# 1_1_4_Interface_board_USB_XBee_RS232.net
KiCad netlist of a schematic drawn in Altium Designer
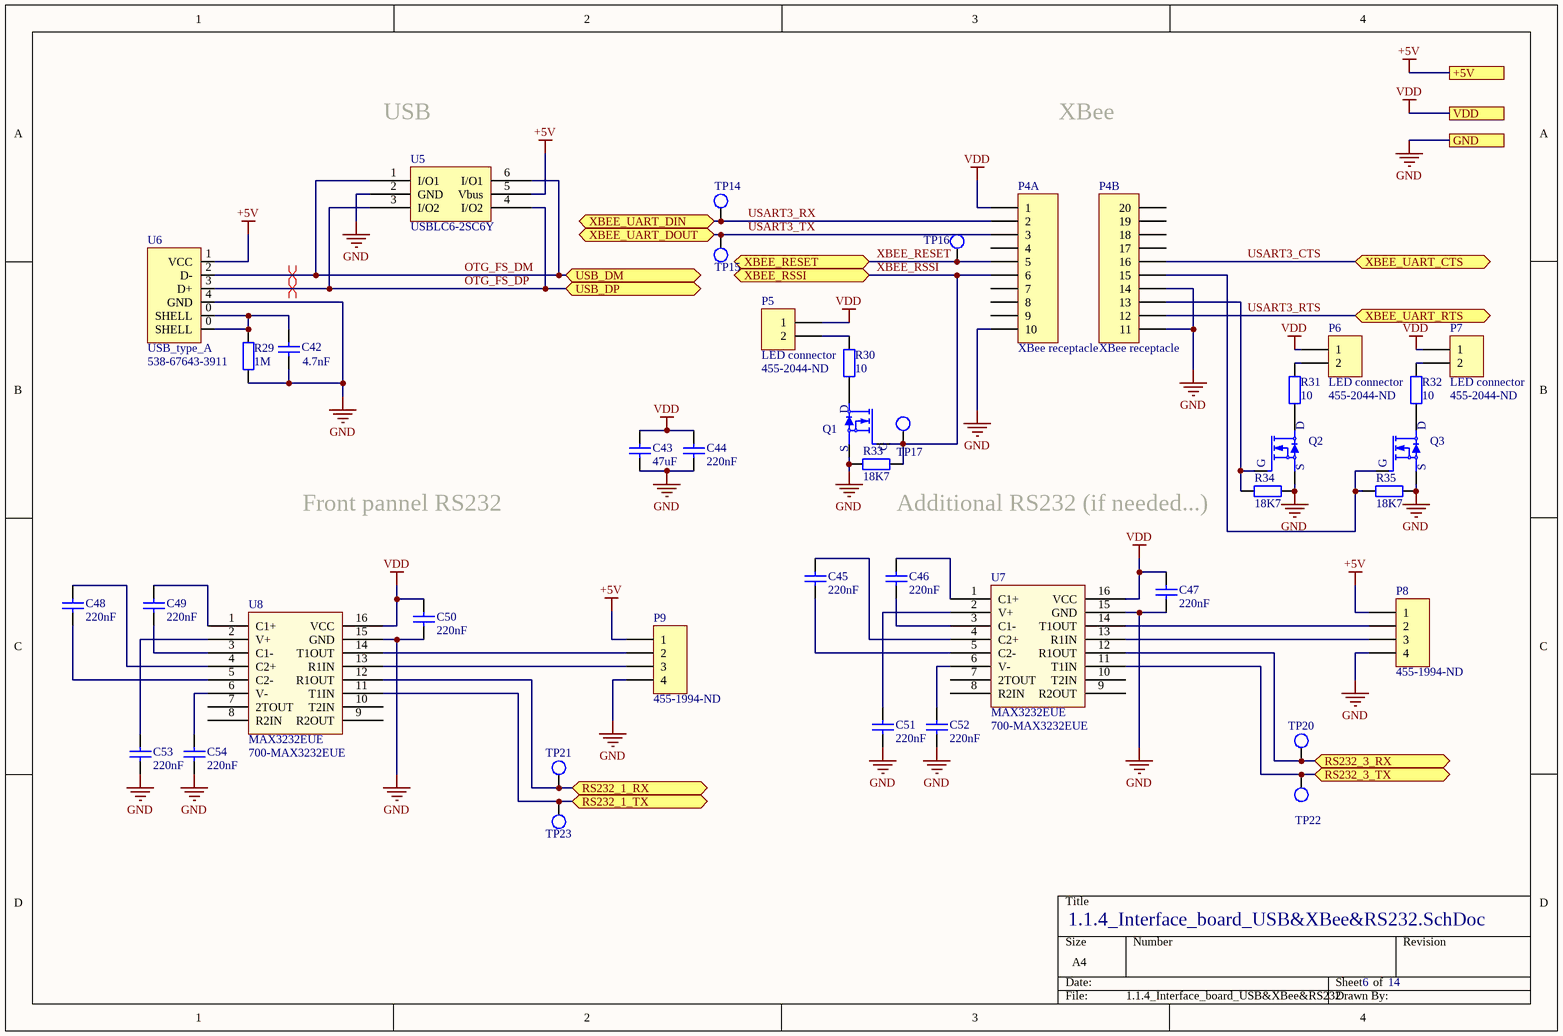
[diagram p0: 1.1.4_Interface_board_USB&XBee&RS232.SchDoc]

(export (version "E")
  (design (tool "Eeschema 10.0.6"))
  (components
    (comp (ref "C42")
      (value "4.7nF")
      (footprint "CAP0603R")
      (description "Capacitor")
      (libsource (lib "Rocket_library") (part "C_4.7nF"))
    )
    (comp (ref "C43")
      (value "47uF")
      (footprint "CAP1206W")
      (description "Capacitor")
      (libsource (lib "Rocket_library") (part "C_47uF_25v_1206"))
    )
    (comp (ref "C44")
      (value "220nF")
      (footprint "CAP0603R")
      (description "Capacitor")
      (libsource (lib "Rocket_library") (part "C_220nF"))
    )
    (comp (ref "C45")
      (value "220nF")
      (footprint "CAP0603R")
      (description "Capacitor")
      (libsource (lib "Rocket_library") (part "C_220nF"))
    )
    (comp (ref "C46")
      (value "220nF")
      (footprint "CAP0603R")
      (description "Capacitor")
      (libsource (lib "Rocket_library") (part "C_220nF"))
    )
    (comp (ref "C47")
      (value "220nF")
      (footprint "CAP0603R")
      (description "Capacitor")
      (libsource (lib "Rocket_library") (part "C_220nF"))
    )
    (comp (ref "C48")
      (value "220nF")
      (footprint "CAP0603R")
      (description "Capacitor")
      (libsource (lib "Rocket_library") (part "C_220nF"))
    )
    (comp (ref "C49")
      (value "220nF")
      (footprint "CAP0603R")
      (description "Capacitor")
      (libsource (lib "Rocket_library") (part "C_220nF"))
    )
    (comp (ref "C50")
      (value "220nF")
      (footprint "CAP0603R")
      (description "Capacitor")
      (libsource (lib "Rocket_library") (part "C_220nF"))
    )
    (comp (ref "C51")
      (value "220nF")
      (footprint "CAP0603R")
      (description "Capacitor")
      (libsource (lib "Rocket_library") (part "C_220nF"))
    )
    (comp (ref "C52")
      (value "220nF")
      (footprint "CAP0603R")
      (description "Capacitor")
      (libsource (lib "Rocket_library") (part "C_220nF"))
    )
    (comp (ref "C53")
      (value "220nF")
      (footprint "CAP0603R")
      (description "Capacitor")
      (libsource (lib "Rocket_library") (part "C_220nF"))
    )
    (comp (ref "C54")
      (value "220nF")
      (footprint "CAP0603R")
      (description "Capacitor")
      (libsource (lib "Rocket_library") (part "C_220nF"))
    )
    (comp (ref "P4")
      (value "XBee receptacle")
      (footprint "XBee receptacle")
      (libsource (lib "Rocket_library") (part "XBee receptacle"))
    )
    (comp (ref "P5")
      (value "LED connector")
      (footprint "CON_JST_XA_ S02B-XASS-1")
      (description "Header 2p JST XA 3A right angle")
      (fields (field (name "SUPPLIER PART NUMBER 1") "455-2044-ND"))
      (libsource (lib "") (part "Header 2p JST XA 3A right angle_1"))
    )
    (comp (ref "P6")
      (value "LED connector")
      (footprint "CON_JST_XA_ S02B-XASS-1")
      (description "Header 2p JST XA 3A right angle")
      (fields (field (name "SUPPLIER PART NUMBER 1") "455-2044-ND"))
      (libsource (lib "Rocket_library") (part "Header 2p JST XA 3A right angle"))
    )
    (comp (ref "P7")
      (value "LED connector")
      (footprint "CON_JST_XA_ S02B-XASS-1")
      (description "Header 2p JST XA 3A right angle")
      (fields (field (name "SUPPLIER PART NUMBER 1") "455-2044-ND"))
      (libsource (lib "Rocket_library") (part "Header 2p JST XA 3A right angle"))
    )
    (comp (ref "P8")
      (value "Header 4p JST XA 3A")
      (footprint "CON_JST_XA_ B04B-XASK")
      (fields (field (name "SUPPLIER PART NUMBER 1") "455-1994-ND"))
      (libsource (lib "Rocket_library") (part "Header 4p JST XA 3A"))
    )
    (comp (ref "P9")
      (value "Header 4p JST XA 3A")
      (footprint "CON_JST_XA_ B04B-XASK")
      (fields (field (name "SUPPLIER PART NUMBER 1") "455-1994-ND"))
      (libsource (lib "Rocket_library") (part "Header 4p JST XA 3A"))
    )
    (comp (ref "Q1")
      (value "MOSFET_N")
      (footprint "SOT-323-3")
      (description "MOSFET N-Ch 20V 1.4A SOT-323-3")
      (libsource (lib "Rocket_library") (part "MOSFET_N_ 20V_1.4A"))
    )
    (comp (ref "Q2")
      (value "MOSFET_N")
      (footprint "SOT-323-3")
      (description "MOSFET N-Ch 20V 1.4A SOT-323-3")
      (libsource (lib "Rocket_library") (part "MOSFET_N_ 20V_1.4A"))
    )
    (comp (ref "Q3")
      (value "MOSFET_N")
      (footprint "SOT-323-3")
      (description "MOSFET N-Ch 20V 1.4A SOT-323-3")
      (libsource (lib "Rocket_library") (part "MOSFET_N_ 20V_1.4A"))
    )
    (comp (ref "R29")
      (value "1M")
      (footprint "0603")
      (description "0.1W 1M")
      (libsource (lib "Rocket_library") (part "R_0603_01W_1M"))
    )
    (comp (ref "R30")
      (value "10")
      (footprint "0603")
      (description "0.25W 10Ohm")
      (libsource (lib "Rocket_library") (part "R_0603_025W_10Ohm"))
    )
    (comp (ref "R31")
      (value "10")
      (footprint "0603")
      (description "0.25W 10Ohm")
      (libsource (lib "Rocket_library") (part "R_0603_025W_10Ohm"))
    )
    (comp (ref "R32")
      (value "10")
      (footprint "0603")
      (description "0.25W 10Ohm")
      (libsource (lib "Rocket_library") (part "R_0603_025W_10Ohm"))
    )
    (comp (ref "R33")
      (value "18K7")
      (footprint "0603")
      (description "0.1W 18K7")
      (libsource (lib "Rocket_library") (part "R_0603_01W_18K7"))
    )
    (comp (ref "R34")
      (value "18K7")
      (footprint "0603")
      (description "0.1W 18K7")
      (libsource (lib "Rocket_library") (part "R_0603_01W_18K7"))
    )
    (comp (ref "R35")
      (value "18K7")
      (footprint "0603")
      (description "0.1W 18K7")
      (libsource (lib "Rocket_library") (part "R_0603_01W_18K7"))
    )
    (comp (ref "TP14")
      (value "Test point")
      (footprint "TP")
      (libsource (lib "Rocket_library") (part "Test point"))
    )
    (comp (ref "TP15")
      (value "Test point")
      (footprint "TP")
      (libsource (lib "Rocket_library") (part "Test point"))
    )
    (comp (ref "TP16")
      (value "Test point")
      (footprint "TP")
      (libsource (lib "Rocket_library") (part "Test point"))
    )
    (comp (ref "TP17")
      (value "Test point")
      (footprint "TP")
      (libsource (lib "Rocket_library") (part "Test point"))
    )
    (comp (ref "TP20")
      (value "Test point")
      (footprint "TP")
      (libsource (lib "Rocket_library") (part "Test point"))
    )
    (comp (ref "TP21")
      (value "Test point")
      (footprint "TP")
      (libsource (lib "Rocket_library") (part "Test point"))
    )
    (comp (ref "TP22")
      (value "Test point")
      (footprint "TP")
      (libsource (lib "Rocket_library") (part "Test point"))
    )
    (comp (ref "TP23")
      (value "Test point")
      (footprint "TP")
      (libsource (lib "Rocket_library") (part "Test point"))
    )
    (comp (ref "U5")
      (value "USBLC6-2SC6Y")
      (footprint "SOT23-6L")
      (description "ESD Suppressors")
      (libsource (lib "Rocket_library") (part "USBLC6-2SC6Y"))
    )
    (comp (ref "U6")
      (value "USB_type_A")
      (footprint "USB type A Right angle")
      (description "USB type A")
      (fields (field (name "SUPPLIER PART NUMBER 1") "538-67643-3911"))
      (libsource (lib "Rocket_library") (part "USB_type_A"))
    )
    (comp (ref "U7")
      (value "MAX3232EUE")
      (footprint "TSSOP 16")
      (description "RS-232 Interface IC 3-5.5V 235kbps Transceiver")
      (fields (field (name "SUPPLIER PART NUMBER 1") "700-MAX3232EUE"))
      (libsource (lib "Rocket_library") (part "MAX3232EUE"))
    )
    (comp (ref "U8")
      (value "MAX3232EUE")
      (footprint "TSSOP 16")
      (description "RS-232 Interface IC 3-5.5V 235kbps Transceiver")
      (fields (field (name "SUPPLIER PART NUMBER 1") "700-MAX3232EUE"))
      (libsource (lib "Rocket_library") (part "MAX3232EUE"))
    )
  )
  (nets
    (net (code "1") (name "+5V") (class "Default")
      (node (ref "P8") (pin "1") (pinfunction "1_1") (pintype "passive"))
      (node (ref "P9") (pin "1") (pinfunction "1_1") (pintype "passive"))
      (node (ref "U5") (pin "5") (pinfunction "Vbus_5") (pintype "passive"))
      (node (ref "U6") (pin "1") (pinfunction "VCC_1") (pintype "passive"))
    )
    (net (code "2") (name "/OTG_FS_DM") (class "Default")
      (node (ref "U5") (pin "1") (pinfunction "I/O1_1") (pintype "passive"))
      (node (ref "U5") (pin "6") (pinfunction "I/O1_6") (pintype "passive"))
      (node (ref "U6") (pin "2") (pinfunction "D-_2") (pintype "passive"))
    )
    (net (code "3") (name "/OTG_FS_DP") (class "Default")
      (node (ref "U5") (pin "3") (pinfunction "I/O2_3") (pintype "passive"))
      (node (ref "U5") (pin "4") (pinfunction "I/O2_4") (pintype "passive"))
      (node (ref "U6") (pin "3") (pinfunction "D+_3") (pintype "passive"))
    )
    (net (code "4") (name "/RS232_1_RX") (class "Default")
      (node (ref "TP21") (pin "1") (pinfunction "1_1") (pintype "passive"))
      (node (ref "U8") (pin "12") (pinfunction "R1OUT_12") (pintype "passive"))
    )
    (net (code "5") (name "/RS232_1_TX") (class "Default")
      (node (ref "TP23") (pin "1") (pinfunction "1_1") (pintype "passive"))
      (node (ref "U8") (pin "11") (pinfunction "T1IN_11") (pintype "passive"))
    )
    (net (code "6") (name "/RS232_3_RX") (class "Default")
      (node (ref "TP20") (pin "1") (pinfunction "1_1") (pintype "passive"))
      (node (ref "U7") (pin "12") (pinfunction "R1OUT_12") (pintype "passive"))
    )
    (net (code "7") (name "/RS232_3_TX") (class "Default")
      (node (ref "TP22") (pin "1") (pinfunction "1_1") (pintype "passive"))
      (node (ref "U7") (pin "11") (pinfunction "T1IN_11") (pintype "passive"))
    )
    (net (code "8") (name "/USART3_CTS") (class "Default")
      (node (ref "P4") (pin "16") (pinfunction "16_16") (pintype "passive"))
    )
    (net (code "9") (name "/USART3_RTS") (class "Default")
      (node (ref "P4") (pin "12") (pinfunction "12_12") (pintype "passive"))
    )
    (net (code "10") (name "/USART3_RX") (class "Default")
      (node (ref "P4") (pin "2") (pinfunction "2_2") (pintype "passive"))
      (node (ref "TP14") (pin "1") (pinfunction "1_1") (pintype "passive"))
    )
    (net (code "11") (name "/USART3_TX") (class "Default")
      (node (ref "P4") (pin "3") (pinfunction "3_3") (pintype "passive"))
      (node (ref "TP15") (pin "1") (pinfunction "1_1") (pintype "passive"))
    )
    (net (code "12") (name "/XBEE_RESET") (class "Default")
      (node (ref "P4") (pin "5") (pinfunction "5_5") (pintype "passive"))
      (node (ref "TP16") (pin "1") (pinfunction "1_1") (pintype "passive"))
    )
    (net (code "13") (name "/XBEE_RSSI") (class "Default")
      (node (ref "P4") (pin "6") (pinfunction "6_6") (pintype "passive"))
      (node (ref "Q1") (pin "1") (pinfunction "G_1") (pintype "passive"))
      (node (ref "R33") (pin "1") (pinfunction "1_1") (pintype "passive"))
      (node (ref "TP17") (pin "1") (pinfunction "1_1") (pintype "passive"))
    )
    (net (code "14") (name "GND") (class "Default")
      (node (ref "C42") (pin "1") (pinfunction "1_1") (pintype "passive"))
      (node (ref "C43") (pin "1") (pinfunction "1_1") (pintype "passive"))
      (node (ref "C44") (pin "1") (pinfunction "1_1") (pintype "passive"))
      (node (ref "C47") (pin "1") (pinfunction "1_1") (pintype "passive"))
      (node (ref "C50") (pin "1") (pinfunction "1_1") (pintype "passive"))
      (node (ref "C51") (pin "1") (pinfunction "1_1") (pintype "passive"))
      (node (ref "C52") (pin "1") (pinfunction "1_1") (pintype "passive"))
      (node (ref "C53") (pin "1") (pinfunction "1_1") (pintype "passive"))
      (node (ref "C54") (pin "1") (pinfunction "1_1") (pintype "passive"))
      (node (ref "P4") (pin "10") (pinfunction "10_10") (pintype "passive"))
      (node (ref "P4") (pin "11") (pinfunction "11_11") (pintype "passive"))
      (node (ref "P4") (pin "14") (pinfunction "14_14") (pintype "passive"))
      (node (ref "P8") (pin "4") (pinfunction "4_4") (pintype "passive"))
      (node (ref "P9") (pin "4") (pinfunction "4_4") (pintype "passive"))
      (node (ref "Q1") (pin "2") (pinfunction "S_2") (pintype "passive"))
      (node (ref "Q2") (pin "2") (pinfunction "S_2") (pintype "passive"))
      (node (ref "Q3") (pin "2") (pinfunction "S_2") (pintype "passive"))
      (node (ref "R29") (pin "1") (pinfunction "1_1") (pintype "passive"))
      (node (ref "R33") (pin "2") (pinfunction "2_2") (pintype "passive"))
      (node (ref "R34") (pin "1") (pinfunction "1_1") (pintype "passive"))
      (node (ref "R35") (pin "1") (pinfunction "1_1") (pintype "passive"))
      (node (ref "U5") (pin "2") (pinfunction "GND_2") (pintype "passive"))
      (node (ref "U6") (pin "4") (pinfunction "GND_4") (pintype "passive"))
      (node (ref "U7") (pin "15") (pinfunction "GND_15") (pintype "passive"))
      (node (ref "U8") (pin "15") (pinfunction "GND_15") (pintype "passive"))
    )
    (net (code "15") (name "Net-(P5-Pad2)") (class "Default")
      (node (ref "P5") (pin "2") (pinfunction "2_2") (pintype "passive"))
      (node (ref "R30") (pin "2") (pinfunction "2_2") (pintype "passive"))
    )
    (net (code "16") (name "Net-(P6-Pad2)") (class "Default")
      (node (ref "P6") (pin "2") (pinfunction "2_2") (pintype "passive"))
      (node (ref "R31") (pin "2") (pinfunction "2_2") (pintype "passive"))
    )
    (net (code "17") (name "Net-(P7-Pad2)") (class "Default")
      (node (ref "P7") (pin "2") (pinfunction "2_2") (pintype "passive"))
      (node (ref "R32") (pin "2") (pinfunction "2_2") (pintype "passive"))
    )
    (net (code "18") (name "Net-(Q1-D)") (class "Default")
      (node (ref "Q1") (pin "3") (pinfunction "D_3") (pintype "passive"))
      (node (ref "R30") (pin "1") (pinfunction "1_1") (pintype "passive"))
    )
    (net (code "19") (name "Net-(Q2-D)") (class "Default")
      (node (ref "Q2") (pin "3") (pinfunction "D_3") (pintype "passive"))
      (node (ref "R31") (pin "1") (pinfunction "1_1") (pintype "passive"))
    )
    (net (code "20") (name "Net-(Q2-G)") (class "Default")
      (node (ref "P4") (pin "13") (pinfunction "13_13") (pintype "passive"))
      (node (ref "Q2") (pin "1") (pinfunction "G_1") (pintype "passive"))
      (node (ref "R34") (pin "2") (pinfunction "2_2") (pintype "passive"))
    )
    (net (code "21") (name "Net-(Q3-D)") (class "Default")
      (node (ref "Q3") (pin "3") (pinfunction "D_3") (pintype "passive"))
      (node (ref "R32") (pin "1") (pinfunction "1_1") (pintype "passive"))
    )
    (net (code "22") (name "Net-(Q3-G)") (class "Default")
      (node (ref "P4") (pin "15") (pinfunction "15_15") (pintype "passive"))
      (node (ref "Q3") (pin "1") (pinfunction "G_1") (pintype "passive"))
      (node (ref "R35") (pin "2") (pinfunction "2_2") (pintype "passive"))
    )
    (net (code "23") (name "Net-(U6-SHELL)") (class "Default")
      (node (ref "C42") (pin "2") (pinfunction "2_2") (pintype "passive"))
      (node (ref "R29") (pin "2") (pinfunction "2_2") (pintype "passive"))
      (node (ref "U6") (pin "0") (pinfunction "SHELL_0") (pintype "passive"))
    )
    (net (code "24") (name "Net-(U7-C1+)") (class "Default")
      (node (ref "C46") (pin "2") (pinfunction "2_2") (pintype "passive"))
      (node (ref "U7") (pin "1") (pinfunction "C1+_1") (pintype "passive"))
    )
    (net (code "25") (name "Net-(U7-C1-)") (class "Default")
      (node (ref "C46") (pin "1") (pinfunction "1_1") (pintype "passive"))
      (node (ref "U7") (pin "3") (pinfunction "C1-_3") (pintype "passive"))
    )
    (net (code "26") (name "Net-(U7-C2+)") (class "Default")
      (node (ref "C45") (pin "2") (pinfunction "2_2") (pintype "passive"))
      (node (ref "U7") (pin "4") (pinfunction "C2+_4") (pintype "passive"))
    )
    (net (code "27") (name "Net-(U7-C2-)") (class "Default")
      (node (ref "C45") (pin "1") (pinfunction "1_1") (pintype "passive"))
      (node (ref "U7") (pin "5") (pinfunction "C2-_5") (pintype "passive"))
    )
    (net (code "28") (name "Net-(U7-R1IN)") (class "Default")
      (node (ref "P8") (pin "3") (pinfunction "3_3") (pintype "passive"))
      (node (ref "U7") (pin "13") (pinfunction "R1IN_13") (pintype "passive"))
    )
    (net (code "29") (name "Net-(U7-T1OUT)") (class "Default")
      (node (ref "P8") (pin "2") (pinfunction "2_2") (pintype "passive"))
      (node (ref "U7") (pin "14") (pinfunction "T1OUT_14") (pintype "passive"))
    )
    (net (code "30") (name "Net-(U7-V+)") (class "Default")
      (node (ref "C51") (pin "2") (pinfunction "2_2") (pintype "passive"))
      (node (ref "U7") (pin "2") (pinfunction "V+_2") (pintype "passive"))
    )
    (net (code "31") (name "Net-(U7-V-)") (class "Default")
      (node (ref "C52") (pin "2") (pinfunction "2_2") (pintype "passive"))
      (node (ref "U7") (pin "6") (pinfunction "V-_6") (pintype "passive"))
    )
    (net (code "32") (name "Net-(U8-C1+)") (class "Default")
      (node (ref "C49") (pin "2") (pinfunction "2_2") (pintype "passive"))
      (node (ref "U8") (pin "1") (pinfunction "C1+_1") (pintype "passive"))
    )
    (net (code "33") (name "Net-(U8-C1-)") (class "Default")
      (node (ref "C49") (pin "1") (pinfunction "1_1") (pintype "passive"))
      (node (ref "U8") (pin "3") (pinfunction "C1-_3") (pintype "passive"))
    )
    (net (code "34") (name "Net-(U8-C2+)") (class "Default")
      (node (ref "C48") (pin "2") (pinfunction "2_2") (pintype "passive"))
      (node (ref "U8") (pin "4") (pinfunction "C2+_4") (pintype "passive"))
    )
    (net (code "35") (name "Net-(U8-C2-)") (class "Default")
      (node (ref "C48") (pin "1") (pinfunction "1_1") (pintype "passive"))
      (node (ref "U8") (pin "5") (pinfunction "C2-_5") (pintype "passive"))
    )
    (net (code "36") (name "Net-(U8-R1IN)") (class "Default")
      (node (ref "P9") (pin "3") (pinfunction "3_3") (pintype "passive"))
      (node (ref "U8") (pin "13") (pinfunction "R1IN_13") (pintype "passive"))
    )
    (net (code "37") (name "Net-(U8-T1OUT)") (class "Default")
      (node (ref "P9") (pin "2") (pinfunction "2_2") (pintype "passive"))
      (node (ref "U8") (pin "14") (pinfunction "T1OUT_14") (pintype "passive"))
    )
    (net (code "38") (name "Net-(U8-V+)") (class "Default")
      (node (ref "C53") (pin "2") (pinfunction "2_2") (pintype "passive"))
      (node (ref "U8") (pin "2") (pinfunction "V+_2") (pintype "passive"))
    )
    (net (code "39") (name "Net-(U8-V-)") (class "Default")
      (node (ref "C54") (pin "2") (pinfunction "2_2") (pintype "passive"))
      (node (ref "U8") (pin "6") (pinfunction "V-_6") (pintype "passive"))
    )
    (net (code "40") (name "VDD") (class "Default")
      (node (ref "C43") (pin "2") (pinfunction "2_2") (pintype "passive"))
      (node (ref "C44") (pin "2") (pinfunction "2_2") (pintype "passive"))
      (node (ref "C47") (pin "2") (pinfunction "2_2") (pintype "passive"))
      (node (ref "C50") (pin "2") (pinfunction "2_2") (pintype "passive"))
      (node (ref "P4") (pin "1") (pinfunction "1_1") (pintype "passive"))
      (node (ref "P5") (pin "1") (pinfunction "1_1") (pintype "passive"))
      (node (ref "P6") (pin "1") (pinfunction "1_1") (pintype "passive"))
      (node (ref "P7") (pin "1") (pinfunction "1_1") (pintype "passive"))
      (node (ref "U7") (pin "16") (pinfunction "VCC_16") (pintype "passive"))
      (node (ref "U8") (pin "16") (pinfunction "VCC_16") (pintype "passive"))
    )
    (net (code "41") (name "unconnected-(P4-Pad4)") (class "Default")
      (node (ref "P4") (pin "4") (pinfunction "4_4") (pintype "passive"))
    )
    (net (code "42") (name "unconnected-(P4-Pad7)") (class "Default")
      (node (ref "P4") (pin "7") (pinfunction "7_7") (pintype "passive"))
    )
    (net (code "43") (name "unconnected-(P4-Pad8)") (class "Default")
      (node (ref "P4") (pin "8") (pinfunction "8_8") (pintype "passive"))
    )
    (net (code "44") (name "unconnected-(P4-Pad9)") (class "Default")
      (node (ref "P4") (pin "9") (pinfunction "9_9") (pintype "passive"))
    )
    (net (code "45") (name "unconnected-(P4-Pad17)") (class "Default")
      (node (ref "P4") (pin "17") (pinfunction "17_17") (pintype "passive"))
    )
    (net (code "46") (name "unconnected-(P4-Pad18)") (class "Default")
      (node (ref "P4") (pin "18") (pinfunction "18_18") (pintype "passive"))
    )
    (net (code "47") (name "unconnected-(P4-Pad19)") (class "Default")
      (node (ref "P4") (pin "19") (pinfunction "19_19") (pintype "passive"))
    )
    (net (code "48") (name "unconnected-(P4-Pad20)") (class "Default")
      (node (ref "P4") (pin "20") (pinfunction "20_20") (pintype "passive"))
    )
    (net (code "49") (name "unconnected-(U7-2TOUT-Pad7)") (class "Default")
      (node (ref "U7") (pin "7") (pinfunction "2TOUT_7") (pintype "passive"))
    )
    (net (code "50") (name "unconnected-(U7-R2IN-Pad8)") (class "Default")
      (node (ref "U7") (pin "8") (pinfunction "R2IN_8") (pintype "passive"))
    )
    (net (code "51") (name "unconnected-(U7-R2OUT-Pad9)") (class "Default")
      (node (ref "U7") (pin "9") (pinfunction "R2OUT_9") (pintype "passive"))
    )
    (net (code "52") (name "unconnected-(U7-T2IN-Pad10)") (class "Default")
      (node (ref "U7") (pin "10") (pinfunction "T2IN_10") (pintype "passive"))
    )
    (net (code "53") (name "unconnected-(U8-2TOUT-Pad7)") (class "Default")
      (node (ref "U8") (pin "7") (pinfunction "2TOUT_7") (pintype "passive"))
    )
    (net (code "54") (name "unconnected-(U8-R2IN-Pad8)") (class "Default")
      (node (ref "U8") (pin "8") (pinfunction "R2IN_8") (pintype "passive"))
    )
    (net (code "55") (name "unconnected-(U8-R2OUT-Pad9)") (class "Default")
      (node (ref "U8") (pin "9") (pinfunction "R2OUT_9") (pintype "passive"))
    )
    (net (code "56") (name "unconnected-(U8-T2IN-Pad10)") (class "Default")
      (node (ref "U8") (pin "10") (pinfunction "T2IN_10") (pintype "passive"))
    )
  )
)
